# SCH_clock_rev_b_2022-04-02.net
KiCad netlist of a schematic drawn in EasyEDA
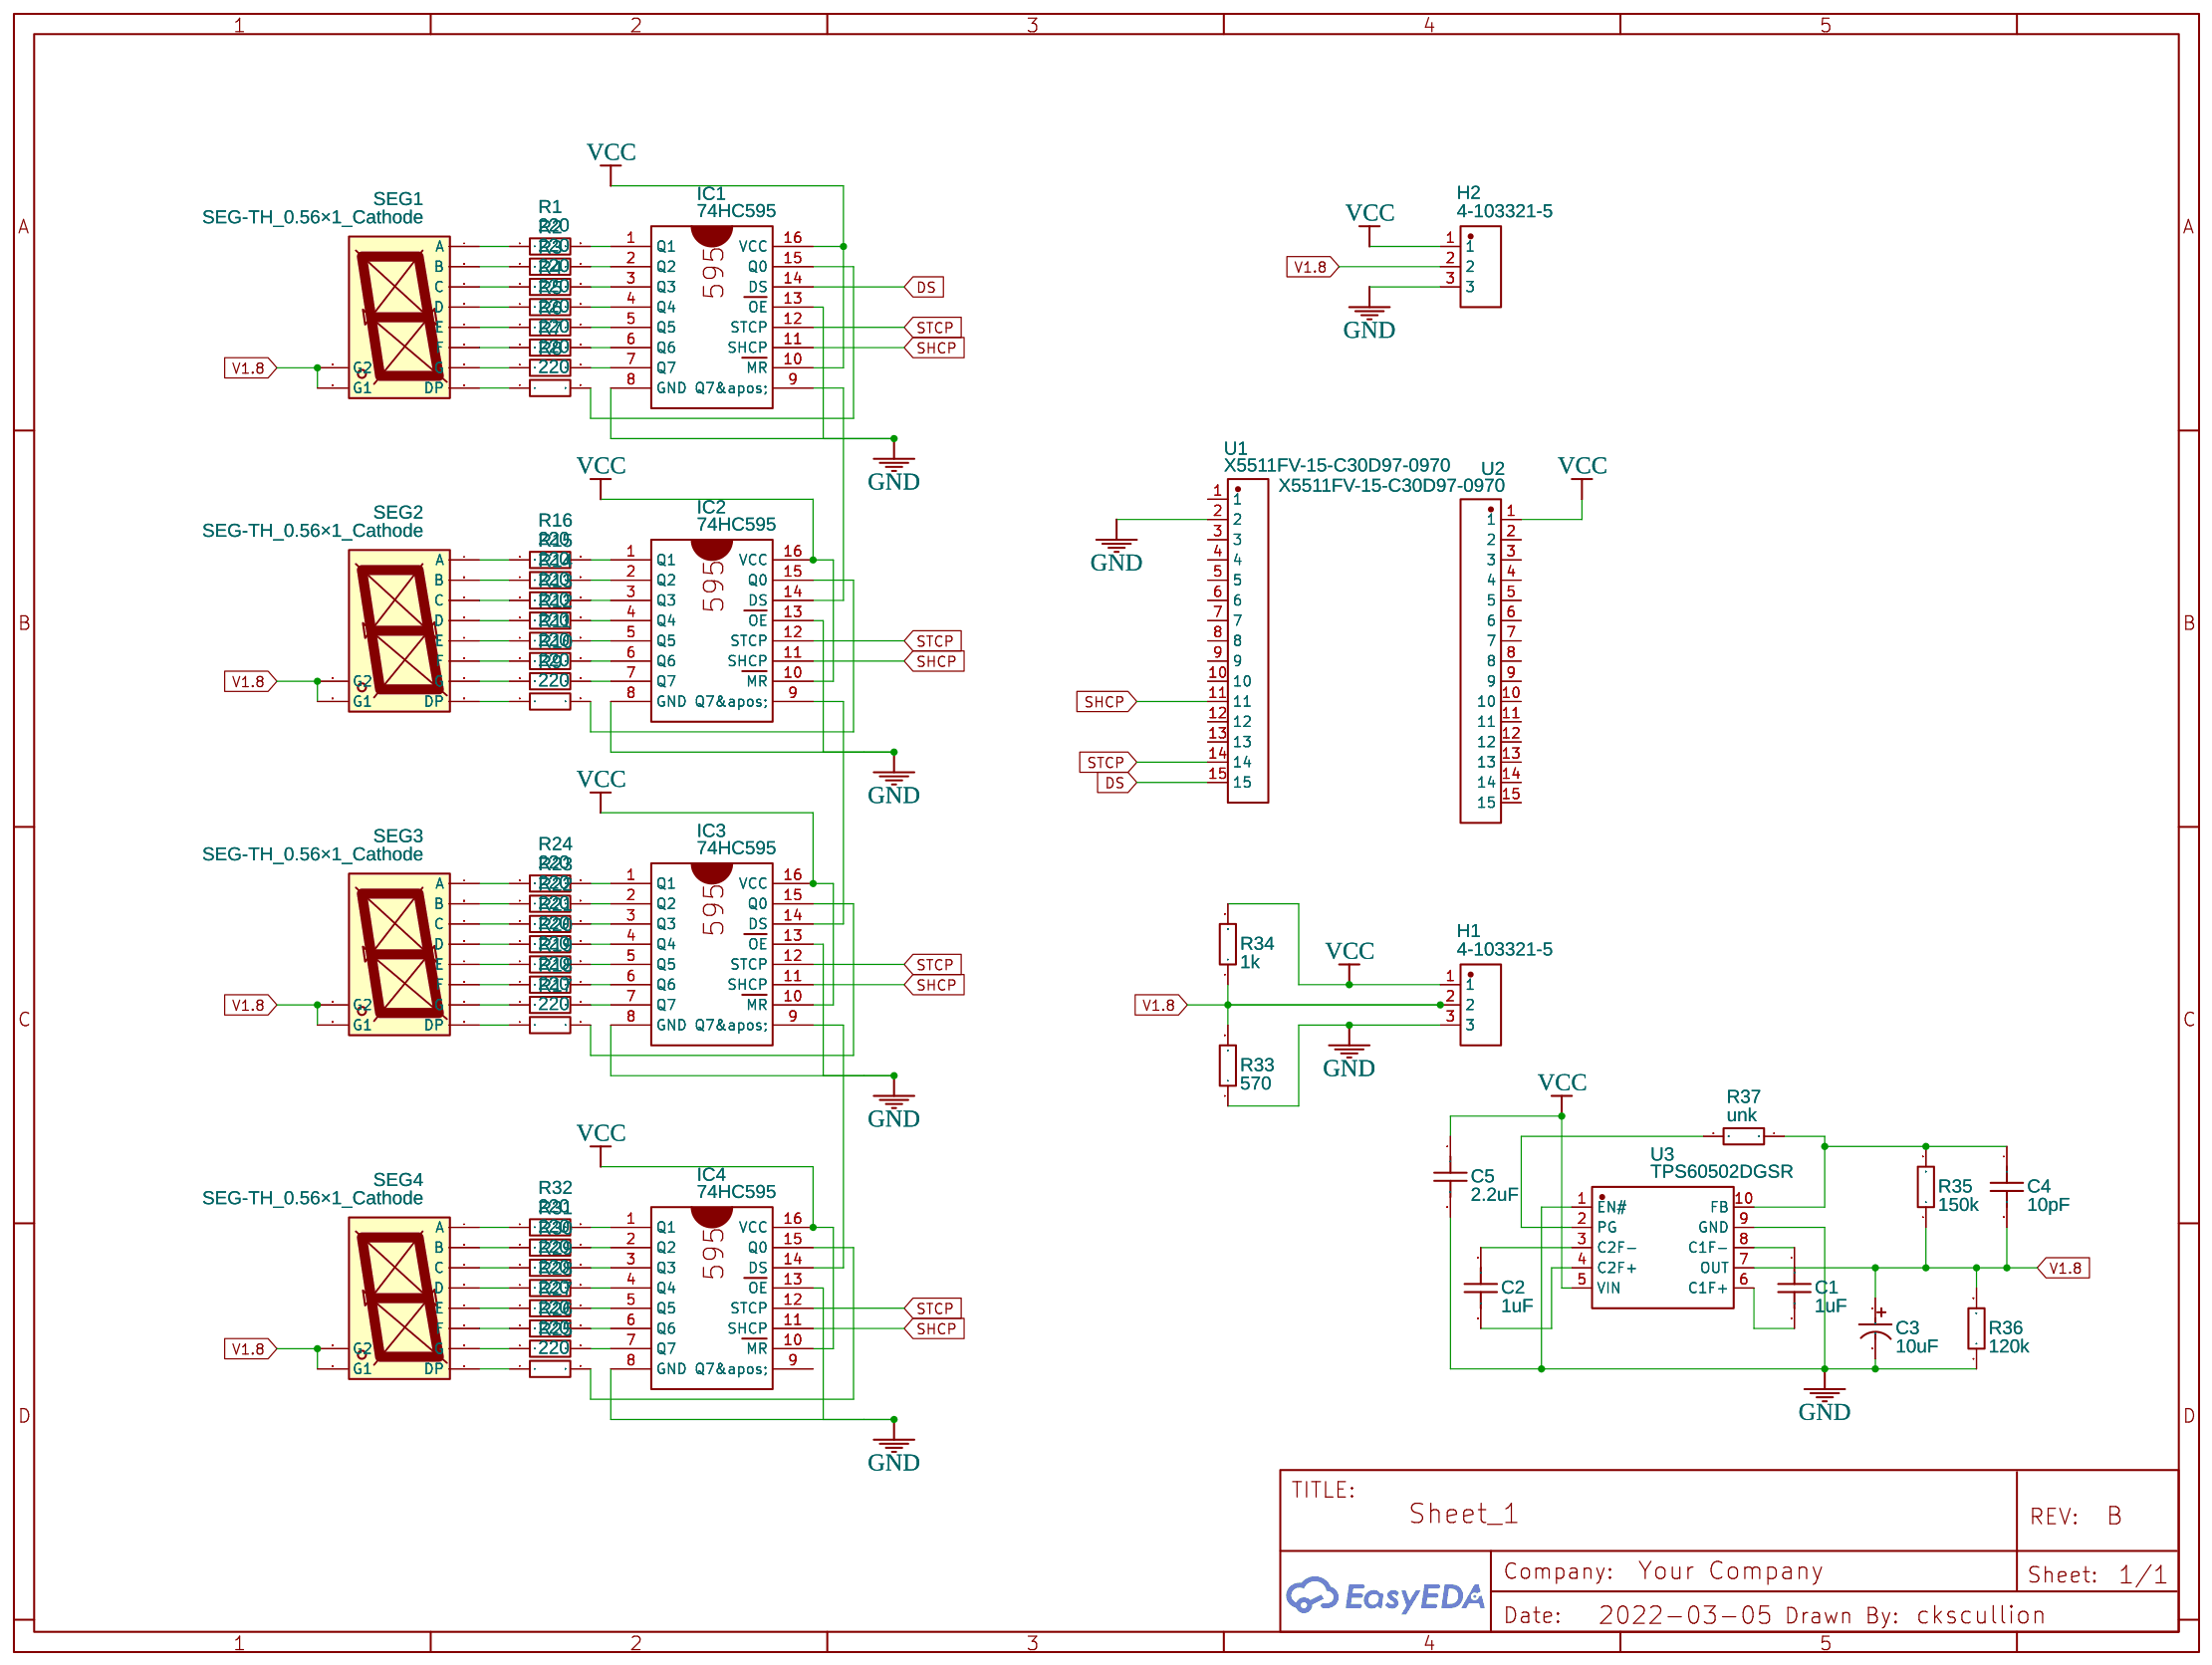
[diagram p0: schematic sheet]

(export (version "E")
  (design (tool "Eeschema 10.0.6"))
  (components
    (comp (ref "C1")
      (value "1uF")
      (fields
        (field (name "BOM_Manufacturer Part") "FK26X7R1H105KRE06")
        (field (name "BOM_Supplier Part") "C2839237")
      )
      (libsource (lib "") (part "FK26X7R1H105KRE06"))
    )
    (comp (ref "C2")
      (value "1uF")
      (fields
        (field (name "BOM_Manufacturer Part") "FK26X7R1H105KRE06")
        (field (name "BOM_Supplier Part") "C2839237")
      )
      (libsource (lib "") (part "FK26X7R1H105KRE06"))
    )
    (comp (ref "C3")
      (value "10uF")
      (fields
        (field (name "BOM_Manufacturer Part") "KF100M050C110A")
        (field (name "BOM_Supplier Part") "C59316")
      )
      (libsource (lib "") (part "KF100M050C110A"))
    )
    (comp (ref "C4")
      (value "10pF")
      (fields
        (field (name "BOM_Manufacturer Part") "FK26X7R1H105KRE06")
        (field (name "BOM_Supplier Part") "C2839237")
      )
      (libsource (lib "") (part "FK26X7R1H105KRE06"))
    )
    (comp (ref "C5")
      (value "2.2uF")
      (fields
        (field (name "BOM_Manufacturer Part") "FK26X7R1H105KRE06")
        (field (name "BOM_Supplier Part") "C2839237")
      )
      (libsource (lib "") (part "FK26X7R1H105KRE06"))
    )
    (comp (ref "H1")
      (value "4-103321-5")
      (fields (field (name "BOM_Supplier Part") "C2895604"))
      (libsource (lib "") (part "4-103321-5"))
    )
    (comp (ref "H2")
      (value "4-103321-5")
      (fields (field (name "BOM_Supplier Part") "C2895604"))
      (libsource (lib "") (part "4-103321-5"))
    )
    (comp (ref "IC1") (value "74HC595") (libsource (lib "") (part "74HC595")))
    (comp (ref "IC2") (value "74HC595") (libsource (lib "") (part "74HC595")))
    (comp (ref "IC3") (value "74HC595") (libsource (lib "") (part "74HC595")))
    (comp (ref "IC4") (value "74HC595") (libsource (lib "") (part "74HC595")))
    (comp (ref "R1")
      (value "220")
      (fields
        (field (name "BOM_Manufacturer Part") "MFR01SF2200A10")
        (field (name "BOM_Supplier Part") "C58706")
      )
      (libsource (lib "") (part "MFR01SF2200A10"))
    )
    (comp (ref "R2")
      (value "220")
      (fields
        (field (name "BOM_Manufacturer Part") "MFR01SF2200A10")
        (field (name "BOM_Supplier Part") "C58706")
      )
      (libsource (lib "") (part "MFR01SF2200A10"))
    )
    (comp (ref "R3")
      (value "220")
      (fields
        (field (name "BOM_Manufacturer Part") "MFR01SF2200A10")
        (field (name "BOM_Supplier Part") "C58706")
      )
      (libsource (lib "") (part "MFR01SF2200A10"))
    )
    (comp (ref "R4")
      (value "220")
      (fields
        (field (name "BOM_Manufacturer Part") "MFR01SF2200A10")
        (field (name "BOM_Supplier Part") "C58706")
      )
      (libsource (lib "") (part "MFR01SF2200A10"))
    )
    (comp (ref "R5")
      (value "220")
      (fields
        (field (name "BOM_Manufacturer Part") "MFR01SF2200A10")
        (field (name "BOM_Supplier Part") "C58706")
      )
      (libsource (lib "") (part "MFR01SF2200A10"))
    )
    (comp (ref "R6")
      (value "220")
      (fields
        (field (name "BOM_Manufacturer Part") "MFR01SF2200A10")
        (field (name "BOM_Supplier Part") "C58706")
      )
      (libsource (lib "") (part "MFR01SF2200A10"))
    )
    (comp (ref "R7")
      (value "220")
      (fields
        (field (name "BOM_Manufacturer Part") "MFR01SF2200A10")
        (field (name "BOM_Supplier Part") "C58706")
      )
      (libsource (lib "") (part "MFR01SF2200A10"))
    )
    (comp (ref "R8")
      (value "220")
      (fields
        (field (name "BOM_Manufacturer Part") "MFR01SF2200A10")
        (field (name "BOM_Supplier Part") "C58706")
      )
      (libsource (lib "") (part "MFR01SF2200A10"))
    )
    (comp (ref "R9")
      (value "220")
      (fields
        (field (name "BOM_Manufacturer Part") "MFR01SF2200A10")
        (field (name "BOM_Supplier Part") "C58706")
      )
      (libsource (lib "") (part "MFR01SF2200A10"))
    )
    (comp (ref "R10")
      (value "220")
      (fields
        (field (name "BOM_Manufacturer Part") "MFR01SF2200A10")
        (field (name "BOM_Supplier Part") "C58706")
      )
      (libsource (lib "") (part "MFR01SF2200A10"))
    )
    (comp (ref "R11")
      (value "220")
      (fields
        (field (name "BOM_Manufacturer Part") "MFR01SF2200A10")
        (field (name "BOM_Supplier Part") "C58706")
      )
      (libsource (lib "") (part "MFR01SF2200A10"))
    )
    (comp (ref "R12")
      (value "220")
      (fields
        (field (name "BOM_Manufacturer Part") "MFR01SF2200A10")
        (field (name "BOM_Supplier Part") "C58706")
      )
      (libsource (lib "") (part "MFR01SF2200A10"))
    )
    (comp (ref "R13")
      (value "220")
      (fields
        (field (name "BOM_Manufacturer Part") "MFR01SF2200A10")
        (field (name "BOM_Supplier Part") "C58706")
      )
      (libsource (lib "") (part "MFR01SF2200A10"))
    )
    (comp (ref "R14")
      (value "220")
      (fields
        (field (name "BOM_Manufacturer Part") "MFR01SF2200A10")
        (field (name "BOM_Supplier Part") "C58706")
      )
      (libsource (lib "") (part "MFR01SF2200A10"))
    )
    (comp (ref "R15")
      (value "220")
      (fields
        (field (name "BOM_Manufacturer Part") "MFR01SF2200A10")
        (field (name "BOM_Supplier Part") "C58706")
      )
      (libsource (lib "") (part "MFR01SF2200A10"))
    )
    (comp (ref "R16")
      (value "220")
      (fields
        (field (name "BOM_Manufacturer Part") "MFR01SF2200A10")
        (field (name "BOM_Supplier Part") "C58706")
      )
      (libsource (lib "") (part "MFR01SF2200A10"))
    )
    (comp (ref "R17")
      (value "220")
      (fields
        (field (name "BOM_Manufacturer Part") "MFR01SF2200A10")
        (field (name "BOM_Supplier Part") "C58706")
      )
      (libsource (lib "") (part "MFR01SF2200A10"))
    )
    (comp (ref "R18")
      (value "220")
      (fields
        (field (name "BOM_Manufacturer Part") "MFR01SF2200A10")
        (field (name "BOM_Supplier Part") "C58706")
      )
      (libsource (lib "") (part "MFR01SF2200A10"))
    )
    (comp (ref "R19")
      (value "220")
      (fields
        (field (name "BOM_Manufacturer Part") "MFR01SF2200A10")
        (field (name "BOM_Supplier Part") "C58706")
      )
      (libsource (lib "") (part "MFR01SF2200A10"))
    )
    (comp (ref "R20")
      (value "220")
      (fields
        (field (name "BOM_Manufacturer Part") "MFR01SF2200A10")
        (field (name "BOM_Supplier Part") "C58706")
      )
      (libsource (lib "") (part "MFR01SF2200A10"))
    )
    (comp (ref "R21")
      (value "220")
      (fields
        (field (name "BOM_Manufacturer Part") "MFR01SF2200A10")
        (field (name "BOM_Supplier Part") "C58706")
      )
      (libsource (lib "") (part "MFR01SF2200A10"))
    )
    (comp (ref "R22")
      (value "220")
      (fields
        (field (name "BOM_Manufacturer Part") "MFR01SF2200A10")
        (field (name "BOM_Supplier Part") "C58706")
      )
      (libsource (lib "") (part "MFR01SF2200A10"))
    )
    (comp (ref "R23")
      (value "220")
      (fields
        (field (name "BOM_Manufacturer Part") "MFR01SF2200A10")
        (field (name "BOM_Supplier Part") "C58706")
      )
      (libsource (lib "") (part "MFR01SF2200A10"))
    )
    (comp (ref "R24")
      (value "220")
      (fields
        (field (name "BOM_Manufacturer Part") "MFR01SF2200A10")
        (field (name "BOM_Supplier Part") "C58706")
      )
      (libsource (lib "") (part "MFR01SF2200A10"))
    )
    (comp (ref "R25")
      (value "220")
      (fields
        (field (name "BOM_Manufacturer Part") "MFR01SF2200A10")
        (field (name "BOM_Supplier Part") "C58706")
      )
      (libsource (lib "") (part "MFR01SF2200A10"))
    )
    (comp (ref "R26")
      (value "220")
      (fields
        (field (name "BOM_Manufacturer Part") "MFR01SF2200A10")
        (field (name "BOM_Supplier Part") "C58706")
      )
      (libsource (lib "") (part "MFR01SF2200A10"))
    )
    (comp (ref "R27")
      (value "220")
      (fields
        (field (name "BOM_Manufacturer Part") "MFR01SF2200A10")
        (field (name "BOM_Supplier Part") "C58706")
      )
      (libsource (lib "") (part "MFR01SF2200A10"))
    )
    (comp (ref "R28")
      (value "220")
      (fields
        (field (name "BOM_Manufacturer Part") "MFR01SF2200A10")
        (field (name "BOM_Supplier Part") "C58706")
      )
      (libsource (lib "") (part "MFR01SF2200A10"))
    )
    (comp (ref "R29")
      (value "220")
      (fields
        (field (name "BOM_Manufacturer Part") "MFR01SF2200A10")
        (field (name "BOM_Supplier Part") "C58706")
      )
      (libsource (lib "") (part "MFR01SF2200A10"))
    )
    (comp (ref "R30")
      (value "220")
      (fields
        (field (name "BOM_Manufacturer Part") "MFR01SF2200A10")
        (field (name "BOM_Supplier Part") "C58706")
      )
      (libsource (lib "") (part "MFR01SF2200A10"))
    )
    (comp (ref "R31")
      (value "220")
      (fields
        (field (name "BOM_Manufacturer Part") "MFR01SF2200A10")
        (field (name "BOM_Supplier Part") "C58706")
      )
      (libsource (lib "") (part "MFR01SF2200A10"))
    )
    (comp (ref "R32")
      (value "220")
      (fields
        (field (name "BOM_Manufacturer Part") "MFR01SF2200A10")
        (field (name "BOM_Supplier Part") "C58706")
      )
      (libsource (lib "") (part "MFR01SF2200A10"))
    )
    (comp (ref "R33")
      (value "570")
      (fields
        (field (name "BOM_Manufacturer Part") "MFR01SF2200A10")
        (field (name "BOM_Supplier Part") "C58706")
      )
      (libsource (lib "") (part "MFR01SF2200A10_1"))
    )
    (comp (ref "R34")
      (value "1k")
      (fields
        (field (name "BOM_Manufacturer Part") "MFR01SF2200A10")
        (field (name "BOM_Supplier Part") "C58706")
      )
      (libsource (lib "") (part "MFR01SF2200A10_1"))
    )
    (comp (ref "R35")
      (value "150k")
      (fields
        (field (name "BOM_Manufacturer Part") "MFR01SF2200A10")
        (field (name "BOM_Supplier Part") "C58706")
      )
      (libsource (lib "") (part "MFR01SF2200A10_1"))
    )
    (comp (ref "R36")
      (value "120k")
      (fields
        (field (name "BOM_Manufacturer Part") "MFR01SF2200A10")
        (field (name "BOM_Supplier Part") "C58706")
      )
      (libsource (lib "") (part "MFR01SF2200A10_1"))
    )
    (comp (ref "R37")
      (value "unk")
      (fields
        (field (name "BOM_Manufacturer Part") "MFR01SF2200A10")
        (field (name "BOM_Supplier Part") "C58706")
      )
      (libsource (lib "") (part "MFR01SF2200A10_2"))
    )
    (comp (ref "SEG1")
      (value "SEG-TH_0.56×1_Cathode")
      (fields (field (name "BOM_Supplier Part") "C8093"))
      (libsource (lib "") (part "SEG-TH_0.56×1_Cathode"))
    )
    (comp (ref "SEG2")
      (value "SEG-TH_0.56×1_Cathode")
      (fields (field (name "BOM_Supplier Part") "C8093"))
      (libsource (lib "") (part "SEG-TH_0.56×1_Cathode"))
    )
    (comp (ref "SEG3")
      (value "SEG-TH_0.56×1_Cathode")
      (fields (field (name "BOM_Supplier Part") "C8093"))
      (libsource (lib "") (part "SEG-TH_0.56×1_Cathode"))
    )
    (comp (ref "SEG4")
      (value "SEG-TH_0.56×1_Cathode")
      (fields (field (name "BOM_Supplier Part") "C8093"))
      (libsource (lib "") (part "SEG-TH_0.56×1_Cathode"))
    )
    (comp (ref "U1")
      (value "X5511FV-15-C30D97-0970")
      (fields (field (name "BOM_Supplier Part") "C2883481"))
      (libsource (lib "") (part "X5511FV-15-C30D97-0970_1"))
    )
    (comp (ref "U2")
      (value "X5511FV-15-C30D97-0970")
      (fields (field (name "BOM_Supplier Part") "C2883481"))
      (libsource (lib "") (part "X5511FV-15-C30D97-0970"))
    )
    (comp (ref "U3")
      (value "TPS60502DGSR")
      (fields (field (name "BOM_Supplier Part") "C2071093"))
      (libsource (lib "") (part "TPS60502DGSR"))
    )
  )
  (nets
    (net (code "1") (name "DS") (class "Default")
      (node (ref "IC1") (pin "14") (pinfunction "DS_14") (pintype "unspecified"))
      (node (ref "U1") (pin "15") (pinfunction "15_15") (pintype "unspecified"))
    )
    (net (code "2") (name "GND") (class "Default")
      (node (ref "C3") (pin "2") (pinfunction "2_2") (pintype "input"))
      (node (ref "C5") (pin "2") (pinfunction "2_2") (pintype "unspecified"))
      (node (ref "H1") (pin "3") (pinfunction "3_3") (pintype "unspecified"))
      (node (ref "H2") (pin "3") (pinfunction "3_3") (pintype "unspecified"))
      (node (ref "IC1") (pin "13") (pinfunction "OE_13") (pintype "unspecified"))
      (node (ref "IC1") (pin "8") (pinfunction "GND_8") (pintype "unspecified"))
      (node (ref "IC2") (pin "13") (pinfunction "OE_13") (pintype "unspecified"))
      (node (ref "IC2") (pin "8") (pinfunction "GND_8") (pintype "unspecified"))
      (node (ref "IC3") (pin "13") (pinfunction "OE_13") (pintype "unspecified"))
      (node (ref "IC3") (pin "8") (pinfunction "GND_8") (pintype "unspecified"))
      (node (ref "IC4") (pin "13") (pinfunction "OE_13") (pintype "unspecified"))
      (node (ref "IC4") (pin "8") (pinfunction "GND_8") (pintype "unspecified"))
      (node (ref "R33") (pin "1") (pinfunction "1_1") (pintype "input"))
      (node (ref "R36") (pin "1") (pinfunction "1_1") (pintype "input"))
      (node (ref "U1") (pin "2") (pinfunction "2_2") (pintype "unspecified"))
      (node (ref "U3") (pin "1") (pinfunction "EN#_1") (pintype "unspecified"))
      (node (ref "U3") (pin "9") (pinfunction "GND_9") (pintype "unspecified"))
    )
    (net (code "3") (name "Net-(IC1-Q0)") (class "Default")
      (node (ref "IC1") (pin "15") (pinfunction "Q0_15") (pintype "unspecified"))
      (node (ref "R8") (pin "2") (pinfunction "2_2") (pintype "input"))
    )
    (net (code "4") (name "Net-(IC1-Q1)") (class "Default")
      (node (ref "IC1") (pin "1") (pinfunction "Q1_1") (pintype "unspecified"))
      (node (ref "R1") (pin "2") (pinfunction "2_2") (pintype "input"))
    )
    (net (code "5") (name "Net-(IC1-Q2)") (class "Default")
      (node (ref "IC1") (pin "2") (pinfunction "Q2_2") (pintype "unspecified"))
      (node (ref "R2") (pin "2") (pinfunction "2_2") (pintype "input"))
    )
    (net (code "6") (name "Net-(IC1-Q3)") (class "Default")
      (node (ref "IC1") (pin "3") (pinfunction "Q3_3") (pintype "unspecified"))
      (node (ref "R3") (pin "2") (pinfunction "2_2") (pintype "input"))
    )
    (net (code "7") (name "Net-(IC1-Q4)") (class "Default")
      (node (ref "IC1") (pin "4") (pinfunction "Q4_4") (pintype "unspecified"))
      (node (ref "R4") (pin "2") (pinfunction "2_2") (pintype "input"))
    )
    (net (code "8") (name "Net-(IC1-Q5)") (class "Default")
      (node (ref "IC1") (pin "5") (pinfunction "Q5_5") (pintype "unspecified"))
      (node (ref "R5") (pin "2") (pinfunction "2_2") (pintype "input"))
    )
    (net (code "9") (name "Net-(IC1-Q6)") (class "Default")
      (node (ref "IC1") (pin "6") (pinfunction "Q6_6") (pintype "unspecified"))
      (node (ref "R6") (pin "2") (pinfunction "2_2") (pintype "input"))
    )
    (net (code "10") (name "Net-(IC1-Q7&apos;)") (class "Default")
      (node (ref "IC1") (pin "9") (pinfunction "Q7&apos;_9") (pintype "unspecified"))
      (node (ref "IC2") (pin "14") (pinfunction "DS_14") (pintype "unspecified"))
    )
    (net (code "11") (name "Net-(IC1-Q7)") (class "Default")
      (node (ref "IC1") (pin "7") (pinfunction "Q7_7") (pintype "unspecified"))
      (node (ref "R7") (pin "2") (pinfunction "2_2") (pintype "input"))
    )
    (net (code "12") (name "Net-(IC2-Q0)") (class "Default")
      (node (ref "IC2") (pin "15") (pinfunction "Q0_15") (pintype "unspecified"))
      (node (ref "R9") (pin "2") (pinfunction "2_2") (pintype "input"))
    )
    (net (code "13") (name "Net-(IC2-Q1)") (class "Default")
      (node (ref "IC2") (pin "1") (pinfunction "Q1_1") (pintype "unspecified"))
      (node (ref "R16") (pin "2") (pinfunction "2_2") (pintype "input"))
    )
    (net (code "14") (name "Net-(IC2-Q2)") (class "Default")
      (node (ref "IC2") (pin "2") (pinfunction "Q2_2") (pintype "unspecified"))
      (node (ref "R15") (pin "2") (pinfunction "2_2") (pintype "input"))
    )
    (net (code "15") (name "Net-(IC2-Q3)") (class "Default")
      (node (ref "IC2") (pin "3") (pinfunction "Q3_3") (pintype "unspecified"))
      (node (ref "R14") (pin "2") (pinfunction "2_2") (pintype "input"))
    )
    (net (code "16") (name "Net-(IC2-Q4)") (class "Default")
      (node (ref "IC2") (pin "4") (pinfunction "Q4_4") (pintype "unspecified"))
      (node (ref "R13") (pin "2") (pinfunction "2_2") (pintype "input"))
    )
    (net (code "17") (name "Net-(IC2-Q5)") (class "Default")
      (node (ref "IC2") (pin "5") (pinfunction "Q5_5") (pintype "unspecified"))
      (node (ref "R12") (pin "2") (pinfunction "2_2") (pintype "input"))
    )
    (net (code "18") (name "Net-(IC2-Q6)") (class "Default")
      (node (ref "IC2") (pin "6") (pinfunction "Q6_6") (pintype "unspecified"))
      (node (ref "R11") (pin "2") (pinfunction "2_2") (pintype "input"))
    )
    (net (code "19") (name "Net-(IC2-Q7&apos;)") (class "Default")
      (node (ref "IC2") (pin "9") (pinfunction "Q7&apos;_9") (pintype "unspecified"))
      (node (ref "IC3") (pin "14") (pinfunction "DS_14") (pintype "unspecified"))
    )
    (net (code "20") (name "Net-(IC2-Q7)") (class "Default")
      (node (ref "IC2") (pin "7") (pinfunction "Q7_7") (pintype "unspecified"))
      (node (ref "R10") (pin "2") (pinfunction "2_2") (pintype "input"))
    )
    (net (code "21") (name "Net-(IC3-Q0)") (class "Default")
      (node (ref "IC3") (pin "15") (pinfunction "Q0_15") (pintype "unspecified"))
      (node (ref "R17") (pin "2") (pinfunction "2_2") (pintype "input"))
    )
    (net (code "22") (name "Net-(IC3-Q1)") (class "Default")
      (node (ref "IC3") (pin "1") (pinfunction "Q1_1") (pintype "unspecified"))
      (node (ref "R24") (pin "2") (pinfunction "2_2") (pintype "input"))
    )
    (net (code "23") (name "Net-(IC3-Q2)") (class "Default")
      (node (ref "IC3") (pin "2") (pinfunction "Q2_2") (pintype "unspecified"))
      (node (ref "R23") (pin "2") (pinfunction "2_2") (pintype "input"))
    )
    (net (code "24") (name "Net-(IC3-Q3)") (class "Default")
      (node (ref "IC3") (pin "3") (pinfunction "Q3_3") (pintype "unspecified"))
      (node (ref "R22") (pin "2") (pinfunction "2_2") (pintype "input"))
    )
    (net (code "25") (name "Net-(IC3-Q4)") (class "Default")
      (node (ref "IC3") (pin "4") (pinfunction "Q4_4") (pintype "unspecified"))
      (node (ref "R21") (pin "2") (pinfunction "2_2") (pintype "input"))
    )
    (net (code "26") (name "Net-(IC3-Q5)") (class "Default")
      (node (ref "IC3") (pin "5") (pinfunction "Q5_5") (pintype "unspecified"))
      (node (ref "R20") (pin "2") (pinfunction "2_2") (pintype "input"))
    )
    (net (code "27") (name "Net-(IC3-Q6)") (class "Default")
      (node (ref "IC3") (pin "6") (pinfunction "Q6_6") (pintype "unspecified"))
      (node (ref "R19") (pin "2") (pinfunction "2_2") (pintype "input"))
    )
    (net (code "28") (name "Net-(IC3-Q7&apos;)") (class "Default")
      (node (ref "IC3") (pin "9") (pinfunction "Q7&apos;_9") (pintype "unspecified"))
      (node (ref "IC4") (pin "14") (pinfunction "DS_14") (pintype "unspecified"))
    )
    (net (code "29") (name "Net-(IC3-Q7)") (class "Default")
      (node (ref "IC3") (pin "7") (pinfunction "Q7_7") (pintype "unspecified"))
      (node (ref "R18") (pin "2") (pinfunction "2_2") (pintype "input"))
    )
    (net (code "30") (name "Net-(IC4-Q0)") (class "Default")
      (node (ref "IC4") (pin "15") (pinfunction "Q0_15") (pintype "unspecified"))
      (node (ref "R25") (pin "2") (pinfunction "2_2") (pintype "input"))
    )
    (net (code "31") (name "Net-(IC4-Q1)") (class "Default")
      (node (ref "IC4") (pin "1") (pinfunction "Q1_1") (pintype "unspecified"))
      (node (ref "R32") (pin "2") (pinfunction "2_2") (pintype "input"))
    )
    (net (code "32") (name "Net-(IC4-Q2)") (class "Default")
      (node (ref "IC4") (pin "2") (pinfunction "Q2_2") (pintype "unspecified"))
      (node (ref "R31") (pin "2") (pinfunction "2_2") (pintype "input"))
    )
    (net (code "33") (name "Net-(IC4-Q3)") (class "Default")
      (node (ref "IC4") (pin "3") (pinfunction "Q3_3") (pintype "unspecified"))
      (node (ref "R30") (pin "2") (pinfunction "2_2") (pintype "input"))
    )
    (net (code "34") (name "Net-(IC4-Q4)") (class "Default")
      (node (ref "IC4") (pin "4") (pinfunction "Q4_4") (pintype "unspecified"))
      (node (ref "R29") (pin "2") (pinfunction "2_2") (pintype "input"))
    )
    (net (code "35") (name "Net-(IC4-Q5)") (class "Default")
      (node (ref "IC4") (pin "5") (pinfunction "Q5_5") (pintype "unspecified"))
      (node (ref "R28") (pin "2") (pinfunction "2_2") (pintype "input"))
    )
    (net (code "36") (name "Net-(IC4-Q6)") (class "Default")
      (node (ref "IC4") (pin "6") (pinfunction "Q6_6") (pintype "unspecified"))
      (node (ref "R27") (pin "2") (pinfunction "2_2") (pintype "input"))
    )
    (net (code "37") (name "Net-(IC4-Q7)") (class "Default")
      (node (ref "IC4") (pin "7") (pinfunction "Q7_7") (pintype "unspecified"))
      (node (ref "R26") (pin "2") (pinfunction "2_2") (pintype "input"))
    )
    (net (code "38") (name "Net-(SEG1-A)") (class "Default")
      (node (ref "R1") (pin "1") (pinfunction "1_1") (pintype "input"))
      (node (ref "SEG1") (pin "7") (pinfunction "A_7") (pintype "unspecified"))
    )
    (net (code "39") (name "Net-(SEG1-B)") (class "Default")
      (node (ref "R2") (pin "1") (pinfunction "1_1") (pintype "input"))
      (node (ref "SEG1") (pin "6") (pinfunction "B_6") (pintype "unspecified"))
    )
    (net (code "40") (name "Net-(SEG1-C)") (class "Default")
      (node (ref "R3") (pin "1") (pinfunction "1_1") (pintype "input"))
      (node (ref "SEG1") (pin "4") (pinfunction "C_4") (pintype "unspecified"))
    )
    (net (code "41") (name "Net-(SEG1-D)") (class "Default")
      (node (ref "R4") (pin "1") (pinfunction "1_1") (pintype "input"))
      (node (ref "SEG1") (pin "2") (pinfunction "D_2") (pintype "unspecified"))
    )
    (net (code "42") (name "Net-(SEG1-DP)") (class "Default")
      (node (ref "R8") (pin "1") (pinfunction "1_1") (pintype "input"))
      (node (ref "SEG1") (pin "5") (pinfunction "DP_5") (pintype "unspecified"))
    )
    (net (code "43") (name "Net-(SEG1-E)") (class "Default")
      (node (ref "R5") (pin "1") (pinfunction "1_1") (pintype "input"))
      (node (ref "SEG1") (pin "1") (pinfunction "E_1") (pintype "unspecified"))
    )
    (net (code "44") (name "Net-(SEG1-F)") (class "Default")
      (node (ref "R6") (pin "1") (pinfunction "1_1") (pintype "input"))
      (node (ref "SEG1") (pin "9") (pinfunction "F_9") (pintype "unspecified"))
    )
    (net (code "45") (name "Net-(SEG1-G)") (class "Default")
      (node (ref "R7") (pin "1") (pinfunction "1_1") (pintype "input"))
      (node (ref "SEG1") (pin "10") (pinfunction "G_10") (pintype "unspecified"))
    )
    (net (code "46") (name "Net-(SEG2-A)") (class "Default")
      (node (ref "R16") (pin "1") (pinfunction "1_1") (pintype "input"))
      (node (ref "SEG2") (pin "7") (pinfunction "A_7") (pintype "unspecified"))
    )
    (net (code "47") (name "Net-(SEG2-B)") (class "Default")
      (node (ref "R15") (pin "1") (pinfunction "1_1") (pintype "input"))
      (node (ref "SEG2") (pin "6") (pinfunction "B_6") (pintype "unspecified"))
    )
    (net (code "48") (name "Net-(SEG2-C)") (class "Default")
      (node (ref "R14") (pin "1") (pinfunction "1_1") (pintype "input"))
      (node (ref "SEG2") (pin "4") (pinfunction "C_4") (pintype "unspecified"))
    )
    (net (code "49") (name "Net-(SEG2-D)") (class "Default")
      (node (ref "R13") (pin "1") (pinfunction "1_1") (pintype "input"))
      (node (ref "SEG2") (pin "2") (pinfunction "D_2") (pintype "unspecified"))
    )
    (net (code "50") (name "Net-(SEG2-DP)") (class "Default")
      (node (ref "R9") (pin "1") (pinfunction "1_1") (pintype "input"))
      (node (ref "SEG2") (pin "5") (pinfunction "DP_5") (pintype "unspecified"))
    )
    (net (code "51") (name "Net-(SEG2-E)") (class "Default")
      (node (ref "R12") (pin "1") (pinfunction "1_1") (pintype "input"))
      (node (ref "SEG2") (pin "1") (pinfunction "E_1") (pintype "unspecified"))
    )
    (net (code "52") (name "Net-(SEG2-F)") (class "Default")
      (node (ref "R11") (pin "1") (pinfunction "1_1") (pintype "input"))
      (node (ref "SEG2") (pin "9") (pinfunction "F_9") (pintype "unspecified"))
    )
    (net (code "53") (name "Net-(SEG2-G)") (class "Default")
      (node (ref "R10") (pin "1") (pinfunction "1_1") (pintype "input"))
      (node (ref "SEG2") (pin "10") (pinfunction "G_10") (pintype "unspecified"))
    )
    (net (code "54") (name "Net-(SEG3-A)") (class "Default")
      (node (ref "R24") (pin "1") (pinfunction "1_1") (pintype "input"))
      (node (ref "SEG3") (pin "7") (pinfunction "A_7") (pintype "unspecified"))
    )
    (net (code "55") (name "Net-(SEG3-B)") (class "Default")
      (node (ref "R23") (pin "1") (pinfunction "1_1") (pintype "input"))
      (node (ref "SEG3") (pin "6") (pinfunction "B_6") (pintype "unspecified"))
    )
    (net (code "56") (name "Net-(SEG3-C)") (class "Default")
      (node (ref "R22") (pin "1") (pinfunction "1_1") (pintype "input"))
      (node (ref "SEG3") (pin "4") (pinfunction "C_4") (pintype "unspecified"))
    )
    (net (code "57") (name "Net-(SEG3-D)") (class "Default")
      (node (ref "R21") (pin "1") (pinfunction "1_1") (pintype "input"))
      (node (ref "SEG3") (pin "2") (pinfunction "D_2") (pintype "unspecified"))
    )
    (net (code "58") (name "Net-(SEG3-DP)") (class "Default")
      (node (ref "R17") (pin "1") (pinfunction "1_1") (pintype "input"))
      (node (ref "SEG3") (pin "5") (pinfunction "DP_5") (pintype "unspecified"))
    )
    (net (code "59") (name "Net-(SEG3-E)") (class "Default")
      (node (ref "R20") (pin "1") (pinfunction "1_1") (pintype "input"))
      (node (ref "SEG3") (pin "1") (pinfunction "E_1") (pintype "unspecified"))
    )
    (net (code "60") (name "Net-(SEG3-F)") (class "Default")
      (node (ref "R19") (pin "1") (pinfunction "1_1") (pintype "input"))
      (node (ref "SEG3") (pin "9") (pinfunction "F_9") (pintype "unspecified"))
    )
    (net (code "61") (name "Net-(SEG3-G)") (class "Default")
      (node (ref "R18") (pin "1") (pinfunction "1_1") (pintype "input"))
      (node (ref "SEG3") (pin "10") (pinfunction "G_10") (pintype "unspecified"))
    )
    (net (code "62") (name "Net-(SEG4-A)") (class "Default")
      (node (ref "R32") (pin "1") (pinfunction "1_1") (pintype "input"))
      (node (ref "SEG4") (pin "7") (pinfunction "A_7") (pintype "unspecified"))
    )
    (net (code "63") (name "Net-(SEG4-B)") (class "Default")
      (node (ref "R31") (pin "1") (pinfunction "1_1") (pintype "input"))
      (node (ref "SEG4") (pin "6") (pinfunction "B_6") (pintype "unspecified"))
    )
    (net (code "64") (name "Net-(SEG4-C)") (class "Default")
      (node (ref "R30") (pin "1") (pinfunction "1_1") (pintype "input"))
      (node (ref "SEG4") (pin "4") (pinfunction "C_4") (pintype "unspecified"))
    )
    (net (code "65") (name "Net-(SEG4-D)") (class "Default")
      (node (ref "R29") (pin "1") (pinfunction "1_1") (pintype "input"))
      (node (ref "SEG4") (pin "2") (pinfunction "D_2") (pintype "unspecified"))
    )
    (net (code "66") (name "Net-(SEG4-DP)") (class "Default")
      (node (ref "R25") (pin "1") (pinfunction "1_1") (pintype "input"))
      (node (ref "SEG4") (pin "5") (pinfunction "DP_5") (pintype "unspecified"))
    )
    (net (code "67") (name "Net-(SEG4-E)") (class "Default")
      (node (ref "R28") (pin "1") (pinfunction "1_1") (pintype "input"))
      (node (ref "SEG4") (pin "1") (pinfunction "E_1") (pintype "unspecified"))
    )
    (net (code "68") (name "Net-(SEG4-F)") (class "Default")
      (node (ref "R27") (pin "1") (pinfunction "1_1") (pintype "input"))
      (node (ref "SEG4") (pin "9") (pinfunction "F_9") (pintype "unspecified"))
    )
    (net (code "69") (name "Net-(SEG4-G)") (class "Default")
      (node (ref "R26") (pin "1") (pinfunction "1_1") (pintype "input"))
      (node (ref "SEG4") (pin "10") (pinfunction "G_10") (pintype "unspecified"))
    )
    (net (code "70") (name "Net-(U3-C1F+)") (class "Default")
      (node (ref "C1") (pin "2") (pinfunction "2_2") (pintype "unspecified"))
      (node (ref "U3") (pin "6") (pinfunction "C1F+_6") (pintype "unspecified"))
    )
    (net (code "71") (name "Net-(U3-C1F-)") (class "Default")
      (node (ref "C1") (pin "1") (pinfunction "1_1") (pintype "unspecified"))
      (node (ref "U3") (pin "8") (pinfunction "C1F-_8") (pintype "unspecified"))
    )
    (net (code "72") (name "Net-(U3-C2F+)") (class "Default")
      (node (ref "C2") (pin "2") (pinfunction "2_2") (pintype "unspecified"))
      (node (ref "U3") (pin "4") (pinfunction "C2F+_4") (pintype "unspecified"))
    )
    (net (code "73") (name "Net-(U3-C2F−)") (class "Default")
      (node (ref "C2") (pin "1") (pinfunction "1_1") (pintype "unspecified"))
      (node (ref "U3") (pin "3") (pinfunction "C2F−_3") (pintype "unspecified"))
    )
    (net (code "74") (name "Net-(U3-FB)") (class "Default")
      (node (ref "C4") (pin "1") (pinfunction "1_1") (pintype "unspecified"))
      (node (ref "R35") (pin "2") (pinfunction "2_2") (pintype "input"))
      (node (ref "R37") (pin "1") (pinfunction "1_1") (pintype "input"))
      (node (ref "U3") (pin "10") (pinfunction "FB_10") (pintype "unspecified"))
    )
    (net (code "75") (name "Net-(U3-PG)") (class "Default")
      (node (ref "R37") (pin "2") (pinfunction "2_2") (pintype "input"))
      (node (ref "U3") (pin "2") (pinfunction "PG_2") (pintype "unspecified"))
    )
    (net (code "76") (name "SHCP") (class "Default")
      (node (ref "IC1") (pin "11") (pinfunction "SHCP_11") (pintype "unspecified"))
      (node (ref "IC2") (pin "11") (pinfunction "SHCP_11") (pintype "unspecified"))
      (node (ref "IC3") (pin "11") (pinfunction "SHCP_11") (pintype "unspecified"))
      (node (ref "IC4") (pin "11") (pinfunction "SHCP_11") (pintype "unspecified"))
      (node (ref "U1") (pin "11") (pinfunction "11_11") (pintype "unspecified"))
    )
    (net (code "77") (name "STCP") (class "Default")
      (node (ref "IC1") (pin "12") (pinfunction "STCP_12") (pintype "unspecified"))
      (node (ref "IC2") (pin "12") (pinfunction "STCP_12") (pintype "unspecified"))
      (node (ref "IC3") (pin "12") (pinfunction "STCP_12") (pintype "unspecified"))
      (node (ref "IC4") (pin "12") (pinfunction "STCP_12") (pintype "unspecified"))
      (node (ref "U1") (pin "14") (pinfunction "14_14") (pintype "unspecified"))
    )
    (net (code "78") (name "V1.8") (class "Default")
      (node (ref "C3") (pin "1") (pinfunction "1_1") (pintype "input"))
      (node (ref "C4") (pin "2") (pinfunction "2_2") (pintype "unspecified"))
      (node (ref "H1") (pin "2") (pinfunction "2_2") (pintype "unspecified"))
      (node (ref "H2") (pin "2") (pinfunction "2_2") (pintype "unspecified"))
      (node (ref "R33") (pin "2") (pinfunction "2_2") (pintype "input"))
      (node (ref "R34") (pin "1") (pinfunction "1_1") (pintype "input"))
      (node (ref "R35") (pin "1") (pinfunction "1_1") (pintype "input"))
      (node (ref "R36") (pin "2") (pinfunction "2_2") (pintype "input"))
      (node (ref "SEG1") (pin "3") (pinfunction "G1_3") (pintype "unspecified"))
      (node (ref "SEG1") (pin "8") (pinfunction "G2_8") (pintype "unspecified"))
      (node (ref "SEG2") (pin "3") (pinfunction "G1_3") (pintype "unspecified"))
      (node (ref "SEG2") (pin "8") (pinfunction "G2_8") (pintype "unspecified"))
      (node (ref "SEG3") (pin "3") (pinfunction "G1_3") (pintype "unspecified"))
      (node (ref "SEG3") (pin "8") (pinfunction "G2_8") (pintype "unspecified"))
      (node (ref "SEG4") (pin "3") (pinfunction "G1_3") (pintype "unspecified"))
      (node (ref "SEG4") (pin "8") (pinfunction "G2_8") (pintype "unspecified"))
      (node (ref "U3") (pin "7") (pinfunction "OUT_7") (pintype "unspecified"))
    )
    (net (code "79") (name "VCC") (class "Default")
      (node (ref "C5") (pin "1") (pinfunction "1_1") (pintype "unspecified"))
      (node (ref "H1") (pin "1") (pinfunction "1_1") (pintype "unspecified"))
      (node (ref "H2") (pin "1") (pinfunction "1_1") (pintype "unspecified"))
      (node (ref "IC1") (pin "10") (pinfunction "MR_10") (pintype "unspecified"))
      (node (ref "IC1") (pin "16") (pinfunction "VCC_16") (pintype "unspecified"))
      (node (ref "IC2") (pin "10") (pinfunction "MR_10") (pintype "unspecified"))
      (node (ref "IC2") (pin "16") (pinfunction "VCC_16") (pintype "unspecified"))
      (node (ref "IC3") (pin "10") (pinfunction "MR_10") (pintype "unspecified"))
      (node (ref "IC3") (pin "16") (pinfunction "VCC_16") (pintype "unspecified"))
      (node (ref "IC4") (pin "10") (pinfunction "MR_10") (pintype "unspecified"))
      (node (ref "IC4") (pin "16") (pinfunction "VCC_16") (pintype "unspecified"))
      (node (ref "R34") (pin "2") (pinfunction "2_2") (pintype "input"))
      (node (ref "U2") (pin "1") (pinfunction "1_1") (pintype "unspecified"))
      (node (ref "U3") (pin "5") (pinfunction "VIN_5") (pintype "unspecified"))
    )
    (net (code "80") (name "unconnected-(IC4-Q7&apos;-Pad9)") (class "Default")
      (node (ref "IC4") (pin "9") (pinfunction "Q7&apos;_9") (pintype "unspecified"))
    )
    (net (code "81") (name "unconnected-(U1-Pad1)") (class "Default")
      (node (ref "U1") (pin "1") (pinfunction "1_1") (pintype "unspecified"))
    )
    (net (code "82") (name "unconnected-(U1-Pad3)") (class "Default")
      (node (ref "U1") (pin "3") (pinfunction "3_3") (pintype "unspecified"))
    )
    (net (code "83") (name "unconnected-(U1-Pad4)") (class "Default")
      (node (ref "U1") (pin "4") (pinfunction "4_4") (pintype "unspecified"))
    )
    (net (code "84") (name "unconnected-(U1-Pad5)") (class "Default")
      (node (ref "U1") (pin "5") (pinfunction "5_5") (pintype "unspecified"))
    )
    (net (code "85") (name "unconnected-(U1-Pad6)") (class "Default")
      (node (ref "U1") (pin "6") (pinfunction "6_6") (pintype "unspecified"))
    )
    (net (code "86") (name "unconnected-(U1-Pad7)") (class "Default")
      (node (ref "U1") (pin "7") (pinfunction "7_7") (pintype "unspecified"))
    )
    (net (code "87") (name "unconnected-(U1-Pad8)") (class "Default")
      (node (ref "U1") (pin "8") (pinfunction "8_8") (pintype "unspecified"))
    )
    (net (code "88") (name "unconnected-(U1-Pad9)") (class "Default")
      (node (ref "U1") (pin "9") (pinfunction "9_9") (pintype "unspecified"))
    )
    (net (code "89") (name "unconnected-(U1-Pad10)") (class "Default")
      (node (ref "U1") (pin "10") (pinfunction "10_10") (pintype "unspecified"))
    )
    (net (code "90") (name "unconnected-(U1-Pad12)") (class "Default")
      (node (ref "U1") (pin "12") (pinfunction "12_12") (pintype "unspecified"))
    )
    (net (code "91") (name "unconnected-(U1-Pad13)") (class "Default")
      (node (ref "U1") (pin "13") (pinfunction "13_13") (pintype "unspecified"))
    )
    (net (code "92") (name "unconnected-(U2-Pad2)") (class "Default")
      (node (ref "U2") (pin "2") (pinfunction "2_2") (pintype "unspecified"))
    )
    (net (code "93") (name "unconnected-(U2-Pad3)") (class "Default")
      (node (ref "U2") (pin "3") (pinfunction "3_3") (pintype "unspecified"))
    )
    (net (code "94") (name "unconnected-(U2-Pad4)") (class "Default")
      (node (ref "U2") (pin "4") (pinfunction "4_4") (pintype "unspecified"))
    )
    (net (code "95") (name "unconnected-(U2-Pad5)") (class "Default")
      (node (ref "U2") (pin "5") (pinfunction "5_5") (pintype "unspecified"))
    )
    (net (code "96") (name "unconnected-(U2-Pad6)") (class "Default")
      (node (ref "U2") (pin "6") (pinfunction "6_6") (pintype "unspecified"))
    )
    (net (code "97") (name "unconnected-(U2-Pad7)") (class "Default")
      (node (ref "U2") (pin "7") (pinfunction "7_7") (pintype "unspecified"))
    )
    (net (code "98") (name "unconnected-(U2-Pad8)") (class "Default")
      (node (ref "U2") (pin "8") (pinfunction "8_8") (pintype "unspecified"))
    )
    (net (code "99") (name "unconnected-(U2-Pad9)") (class "Default")
      (node (ref "U2") (pin "9") (pinfunction "9_9") (pintype "unspecified"))
    )
    (net (code "100") (name "unconnected-(U2-Pad10)") (class "Default")
      (node (ref "U2") (pin "10") (pinfunction "10_10") (pintype "unspecified"))
    )
    (net (code "101") (name "unconnected-(U2-Pad11)") (class "Default")
      (node (ref "U2") (pin "11") (pinfunction "11_11") (pintype "unspecified"))
    )
    (net (code "102") (name "unconnected-(U2-Pad12)") (class "Default")
      (node (ref "U2") (pin "12") (pinfunction "12_12") (pintype "unspecified"))
    )
    (net (code "103") (name "unconnected-(U2-Pad13)") (class "Default")
      (node (ref "U2") (pin "13") (pinfunction "13_13") (pintype "unspecified"))
    )
    (net (code "104") (name "unconnected-(U2-Pad14)") (class "Default")
      (node (ref "U2") (pin "14") (pinfunction "14_14") (pintype "unspecified"))
    )
    (net (code "105") (name "unconnected-(U2-Pad15)") (class "Default")
      (node (ref "U2") (pin "15") (pinfunction "15_15") (pintype "unspecified"))
    )
  )
)
